# dekatron-sim-4017-a3.net
KiCad netlist of a schematic drawn in EAGLE
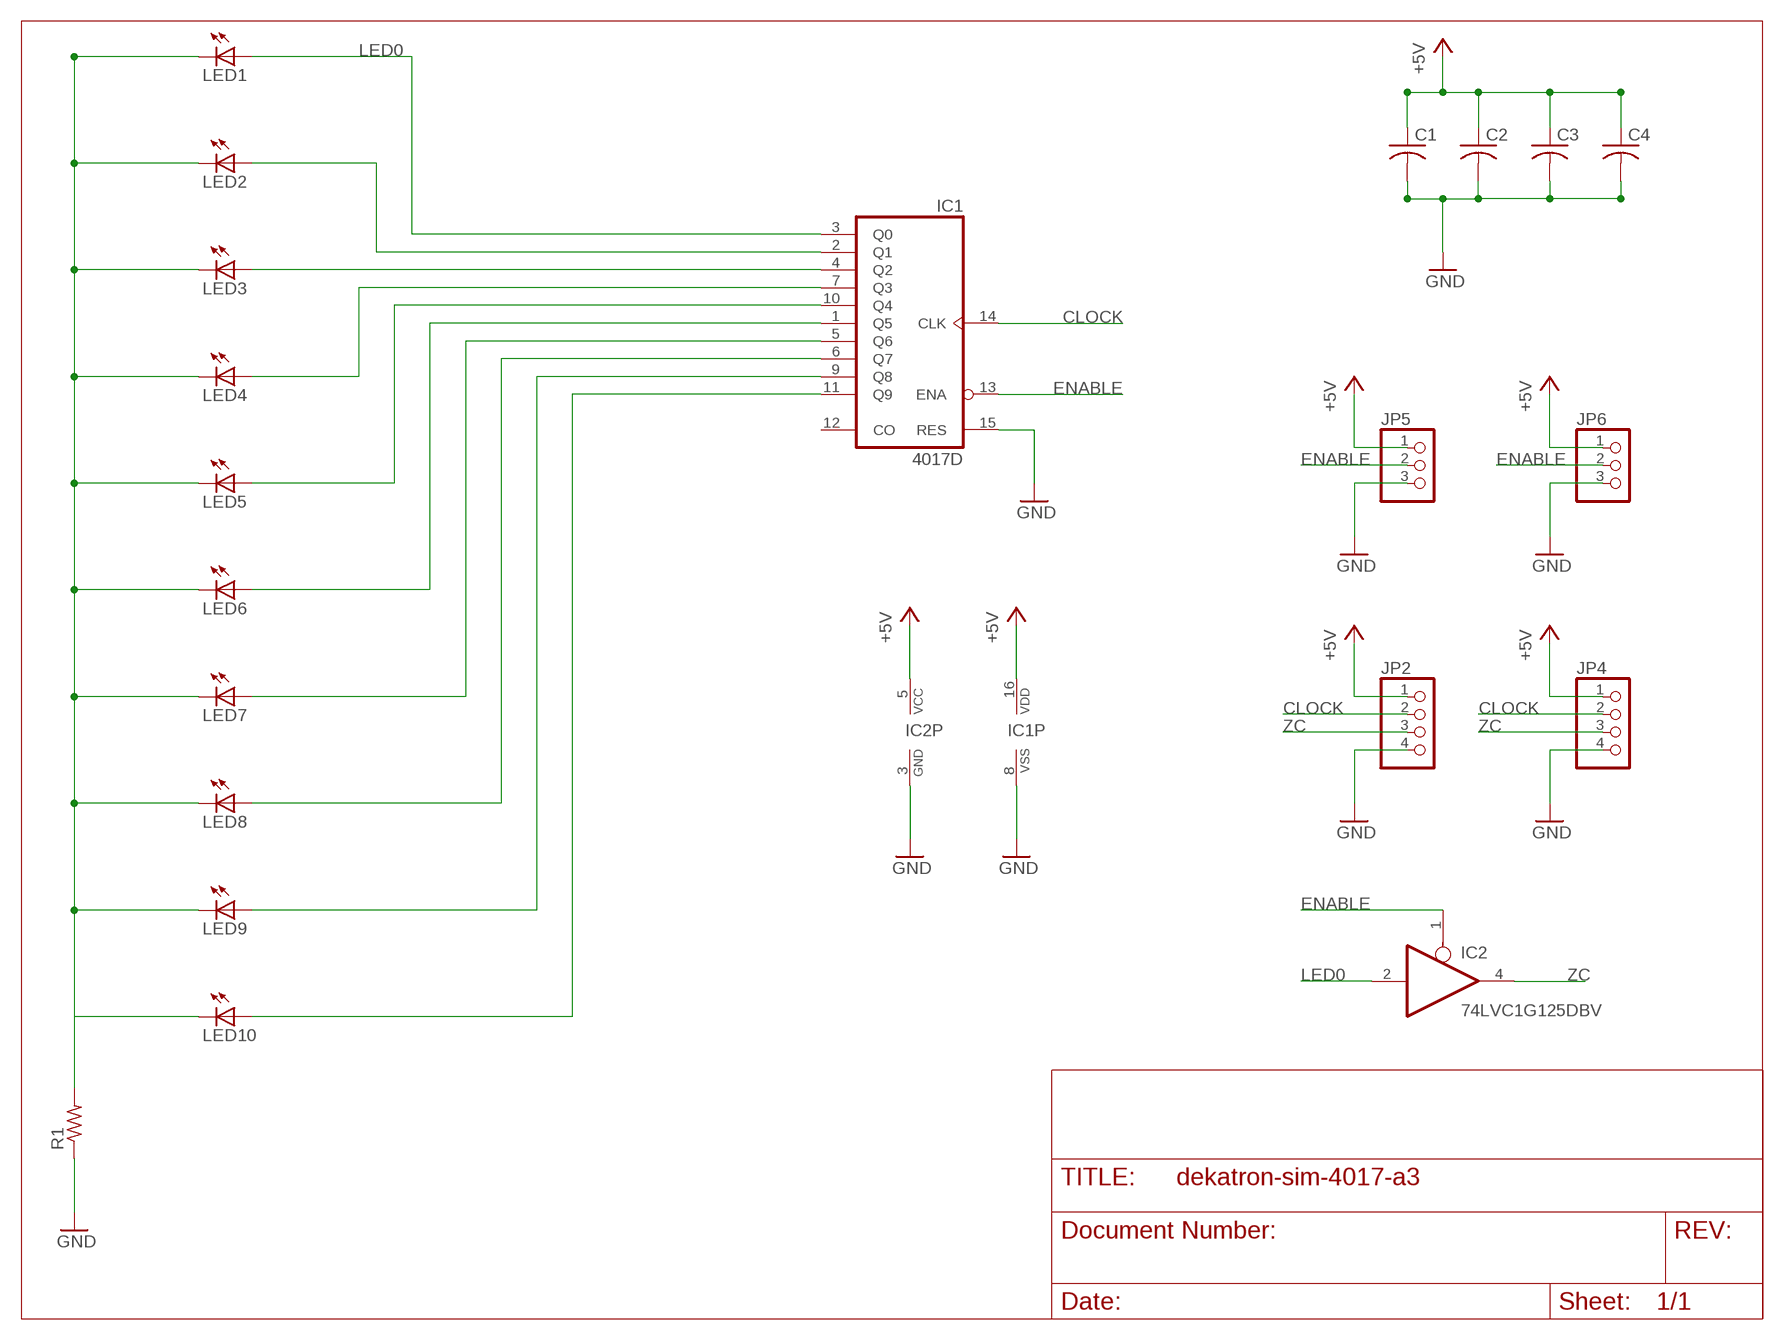
[diagram p0: schematic, sheet 1]

(export (version "E")
  (design (tool "Eeschema 10.0.6"))
  (components
    (comp (ref "C1")
      (value "C-USC0805")
      (footprint "eagle-import:C0805")
      (libsource (lib "eagle-import") (part "C-USC0805"))
    )
    (comp (ref "C2")
      (value "C-USC0805")
      (footprint "eagle-import:C0805")
      (libsource (lib "eagle-import") (part "C-USC0805"))
    )
    (comp (ref "C3")
      (value "C-USC0805")
      (footprint "eagle-import:C0805")
      (libsource (lib "eagle-import") (part "C-USC0805"))
    )
    (comp (ref "C4")
      (value "C-USC0805")
      (footprint "eagle-import:C0805")
      (libsource (lib "eagle-import") (part "C-USC0805"))
    )
    (comp (ref "IC1")
      (value "4017D")
      (footprint "eagle-import:SO16")
      (libsource (lib "eagle-import") (part "4017D"))
    )
    (comp (ref "IC2")
      (value "74LVC1G125DBV")
      (footprint "eagle-import:SOT23-5")
      (libsource (lib "eagle-import") (part "741G125DBVLVC"))
    )
    (comp (ref "JP2")
      (value "PINHD-1X4")
      (footprint "eagle-import:1X04")
      (libsource (lib "eagle-import") (part "PINHD-1X4"))
    )
    (comp (ref "JP4")
      (value "PINHD-1X4")
      (footprint "eagle-import:1X04")
      (libsource (lib "eagle-import") (part "PINHD-1X4"))
    )
    (comp (ref "JP5")
      (value "PINHD-1X3")
      (footprint "eagle-import:1X03")
      (libsource (lib "eagle-import") (part "PINHD-1X3"))
    )
    (comp (ref "JP6")
      (value "PINHD-1X3")
      (footprint "eagle-import:1X03")
      (libsource (lib "eagle-import") (part "PINHD-1X3"))
    )
    (comp (ref "LED1")
      (value "RED")
      (footprint "eagle-import:CHIP-LED0805")
      (libsource (lib "eagle-import") (part "LEDCHIP-LED0805"))
    )
    (comp (ref "LED2")
      (value "RED")
      (footprint "eagle-import:CHIP-LED0805")
      (libsource (lib "eagle-import") (part "LEDCHIP-LED0805"))
    )
    (comp (ref "LED3")
      (value "RED")
      (footprint "eagle-import:CHIP-LED0805")
      (libsource (lib "eagle-import") (part "LEDCHIP-LED0805"))
    )
    (comp (ref "LED4")
      (value "RED")
      (footprint "eagle-import:CHIP-LED0805")
      (libsource (lib "eagle-import") (part "LEDCHIP-LED0805"))
    )
    (comp (ref "LED5")
      (value "RED")
      (footprint "eagle-import:CHIP-LED0805")
      (libsource (lib "eagle-import") (part "LEDCHIP-LED0805"))
    )
    (comp (ref "LED6")
      (value "RED")
      (footprint "eagle-import:CHIP-LED0805")
      (libsource (lib "eagle-import") (part "LEDCHIP-LED0805"))
    )
    (comp (ref "LED7")
      (value "RED")
      (footprint "eagle-import:CHIP-LED0805")
      (libsource (lib "eagle-import") (part "LEDCHIP-LED0805"))
    )
    (comp (ref "LED8")
      (value "RED")
      (footprint "eagle-import:CHIP-LED0805")
      (libsource (lib "eagle-import") (part "LEDCHIP-LED0805"))
    )
    (comp (ref "LED9")
      (value "RED")
      (footprint "eagle-import:CHIP-LED0805")
      (libsource (lib "eagle-import") (part "LEDCHIP-LED0805"))
    )
    (comp (ref "LED10")
      (value "RED")
      (footprint "eagle-import:CHIP-LED0805")
      (libsource (lib "eagle-import") (part "LEDCHIP-LED0805"))
    )
    (comp (ref "R1")
      (value "R-US_R0805")
      (footprint "eagle-import:R0805")
      (libsource (lib "eagle-import") (part "R-US_R0805"))
    )
  )
  (nets
    (net (code "1") (name "+5V") (class "Default")
      (node (ref "C1") (pin "1") (pinfunction "1_1") (pintype "passive"))
      (node (ref "C2") (pin "1") (pinfunction "1_1") (pintype "passive"))
      (node (ref "C3") (pin "1") (pinfunction "1_1") (pintype "passive"))
      (node (ref "C4") (pin "1") (pinfunction "1_1") (pintype "passive"))
      (node (ref "IC1") (pin "16") (pinfunction "VDD_16") (pintype "power_in"))
      (node (ref "IC2") (pin "5") (pinfunction "VCC_5") (pintype "power_in"))
      (node (ref "JP2") (pin "1") (pinfunction "1_1") (pintype "passive"))
      (node (ref "JP4") (pin "1") (pinfunction "1_1") (pintype "passive"))
      (node (ref "JP5") (pin "1") (pinfunction "1_1") (pintype "passive"))
      (node (ref "JP6") (pin "1") (pinfunction "1_1") (pintype "passive"))
    )
    (net (code "2") (name "/CLOCK") (class "Default")
      (node (ref "IC1") (pin "14") (pinfunction "CLK_14") (pintype "input"))
      (node (ref "JP2") (pin "2") (pinfunction "2_2") (pintype "passive"))
      (node (ref "JP4") (pin "2") (pinfunction "2_2") (pintype "passive"))
    )
    (net (code "3") (name "/ENABLE") (class "Default")
      (node (ref "IC1") (pin "13") (pinfunction "ENA_13") (pintype "input"))
      (node (ref "IC2") (pin "1") (pinfunction "OE_1") (pintype "input"))
      (node (ref "JP5") (pin "2") (pinfunction "2_2") (pintype "passive"))
      (node (ref "JP6") (pin "2") (pinfunction "2_2") (pintype "passive"))
    )
    (net (code "4") (name "/LED0") (class "Default")
      (node (ref "IC1") (pin "3") (pinfunction "Q0_3") (pintype "output"))
      (node (ref "IC2") (pin "2") (pinfunction "I_2") (pintype "input"))
      (node (ref "LED1") (pin "A") (pinfunction "A_A") (pintype "passive"))
    )
    (net (code "5") (name "/ZC") (class "Default")
      (node (ref "IC2") (pin "4") (pinfunction "O_4") (pintype "tri_state"))
      (node (ref "JP2") (pin "3") (pinfunction "3_3") (pintype "passive"))
      (node (ref "JP4") (pin "3") (pinfunction "3_3") (pintype "passive"))
    )
    (net (code "6") (name "GND") (class "Default")
      (node (ref "C1") (pin "2") (pinfunction "2_2") (pintype "passive"))
      (node (ref "C2") (pin "2") (pinfunction "2_2") (pintype "passive"))
      (node (ref "C3") (pin "2") (pinfunction "2_2") (pintype "passive"))
      (node (ref "C4") (pin "2") (pinfunction "2_2") (pintype "passive"))
      (node (ref "IC1") (pin "15") (pinfunction "RES_15") (pintype "input"))
      (node (ref "IC1") (pin "8") (pinfunction "VSS_8") (pintype "power_in"))
      (node (ref "IC2") (pin "3") (pinfunction "GND_3") (pintype "power_in"))
      (node (ref "JP2") (pin "4") (pinfunction "4_4") (pintype "passive"))
      (node (ref "JP4") (pin "4") (pinfunction "4_4") (pintype "passive"))
      (node (ref "JP5") (pin "3") (pinfunction "3_3") (pintype "passive"))
      (node (ref "JP6") (pin "3") (pinfunction "3_3") (pintype "passive"))
      (node (ref "R1") (pin "1") (pinfunction "1_1") (pintype "passive"))
    )
    (net (code "7") (name "Net-(IC1A-Q1)") (class "Default")
      (node (ref "IC1") (pin "2") (pinfunction "Q1_2") (pintype "output"))
      (node (ref "LED2") (pin "A") (pinfunction "A_A") (pintype "passive"))
    )
    (net (code "8") (name "Net-(IC1A-Q2)") (class "Default")
      (node (ref "IC1") (pin "4") (pinfunction "Q2_4") (pintype "output"))
      (node (ref "LED3") (pin "A") (pinfunction "A_A") (pintype "passive"))
    )
    (net (code "9") (name "Net-(IC1A-Q3)") (class "Default")
      (node (ref "IC1") (pin "7") (pinfunction "Q3_7") (pintype "output"))
      (node (ref "LED4") (pin "A") (pinfunction "A_A") (pintype "passive"))
    )
    (net (code "10") (name "Net-(IC1A-Q4)") (class "Default")
      (node (ref "IC1") (pin "10") (pinfunction "Q4_10") (pintype "output"))
      (node (ref "LED5") (pin "A") (pinfunction "A_A") (pintype "passive"))
    )
    (net (code "11") (name "Net-(IC1A-Q5)") (class "Default")
      (node (ref "IC1") (pin "1") (pinfunction "Q5_1") (pintype "output"))
      (node (ref "LED6") (pin "A") (pinfunction "A_A") (pintype "passive"))
    )
    (net (code "12") (name "Net-(IC1A-Q6)") (class "Default")
      (node (ref "IC1") (pin "5") (pinfunction "Q6_5") (pintype "output"))
      (node (ref "LED7") (pin "A") (pinfunction "A_A") (pintype "passive"))
    )
    (net (code "13") (name "Net-(IC1A-Q7)") (class "Default")
      (node (ref "IC1") (pin "6") (pinfunction "Q7_6") (pintype "output"))
      (node (ref "LED8") (pin "A") (pinfunction "A_A") (pintype "passive"))
    )
    (net (code "14") (name "Net-(IC1A-Q8)") (class "Default")
      (node (ref "IC1") (pin "9") (pinfunction "Q8_9") (pintype "output"))
      (node (ref "LED9") (pin "A") (pinfunction "A_A") (pintype "passive"))
    )
    (net (code "15") (name "Net-(IC1A-Q9)") (class "Default")
      (node (ref "IC1") (pin "11") (pinfunction "Q9_11") (pintype "output"))
      (node (ref "LED10") (pin "A") (pinfunction "A_A") (pintype "passive"))
    )
    (net (code "16") (name "Net-(LED1-PadC)") (class "Default")
      (node (ref "LED1") (pin "C") (pinfunction "C_C") (pintype "passive"))
      (node (ref "LED10") (pin "C") (pinfunction "C_C") (pintype "passive"))
      (node (ref "LED2") (pin "C") (pinfunction "C_C") (pintype "passive"))
      (node (ref "LED3") (pin "C") (pinfunction "C_C") (pintype "passive"))
      (node (ref "LED4") (pin "C") (pinfunction "C_C") (pintype "passive"))
      (node (ref "LED5") (pin "C") (pinfunction "C_C") (pintype "passive"))
      (node (ref "LED6") (pin "C") (pinfunction "C_C") (pintype "passive"))
      (node (ref "LED7") (pin "C") (pinfunction "C_C") (pintype "passive"))
      (node (ref "LED8") (pin "C") (pinfunction "C_C") (pintype "passive"))
      (node (ref "LED9") (pin "C") (pinfunction "C_C") (pintype "passive"))
      (node (ref "R1") (pin "2") (pinfunction "2_2") (pintype "passive"))
    )
    (net (code "17") (name "unconnected-(IC1A-CO-Pad12)") (class "Default")
      (node (ref "IC1") (pin "12") (pinfunction "CO_12") (pintype "output"))
    )
  )
)
